# Board-Ultrasonic.net
KiCad netlist of a schematic drawn in Altium Designer
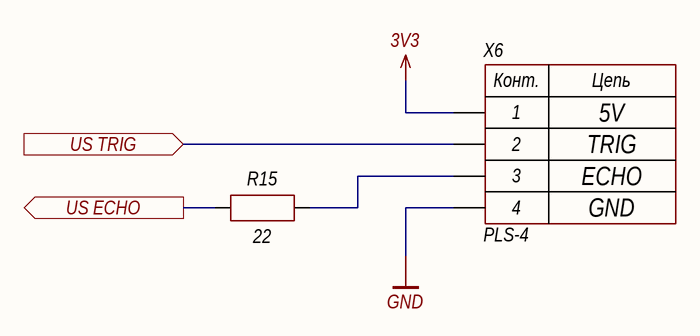
[diagram p0: Board-Ultrasonic.SchDoc]

(export (version "E")
  (design (tool "Eeschema 10.0.6"))
  (components
    (comp (ref "R15")
      (value "22")
      (footprint "CH0402R")
      (fields (field (name "MANUFACTURER") "YAGEO"))
      (libsource (lib "Discrete") (part "Resistor"))
    )
    (comp (ref "X6")
      (value "PLS-4")
      (footprint "CON: PLS-4")
      (libsource (lib "Connectors") (part "4-Connector"))
    )
  )
  (nets
    (net (code "1") (name "/US ECHO") (class "Default")
      (node (ref "R15") (pin "1") (pinfunction "1_1") (pintype "passive"))
    )
    (net (code "2") (name "/US TRIG") (class "Default")
      (node (ref "X6") (pin "2") (pinfunction "2_2") (pintype "passive"))
    )
    (net (code "3") (name "3V3") (class "Default")
      (node (ref "X6") (pin "1") (pinfunction "1_1") (pintype "passive"))
    )
    (net (code "4") (name "GND") (class "Default")
      (node (ref "X6") (pin "4") (pinfunction "4_4") (pintype "passive"))
    )
    (net (code "5") (name "Net-(R15-Pad2)") (class "Default")
      (node (ref "R15") (pin "2") (pinfunction "2_2") (pintype "passive"))
      (node (ref "X6") (pin "3") (pinfunction "3_3") (pintype "passive"))
    )
  )
)
